# RPi_SPI_inputs_v01.net
KiCad netlist of a schematic drawn in EAGLE
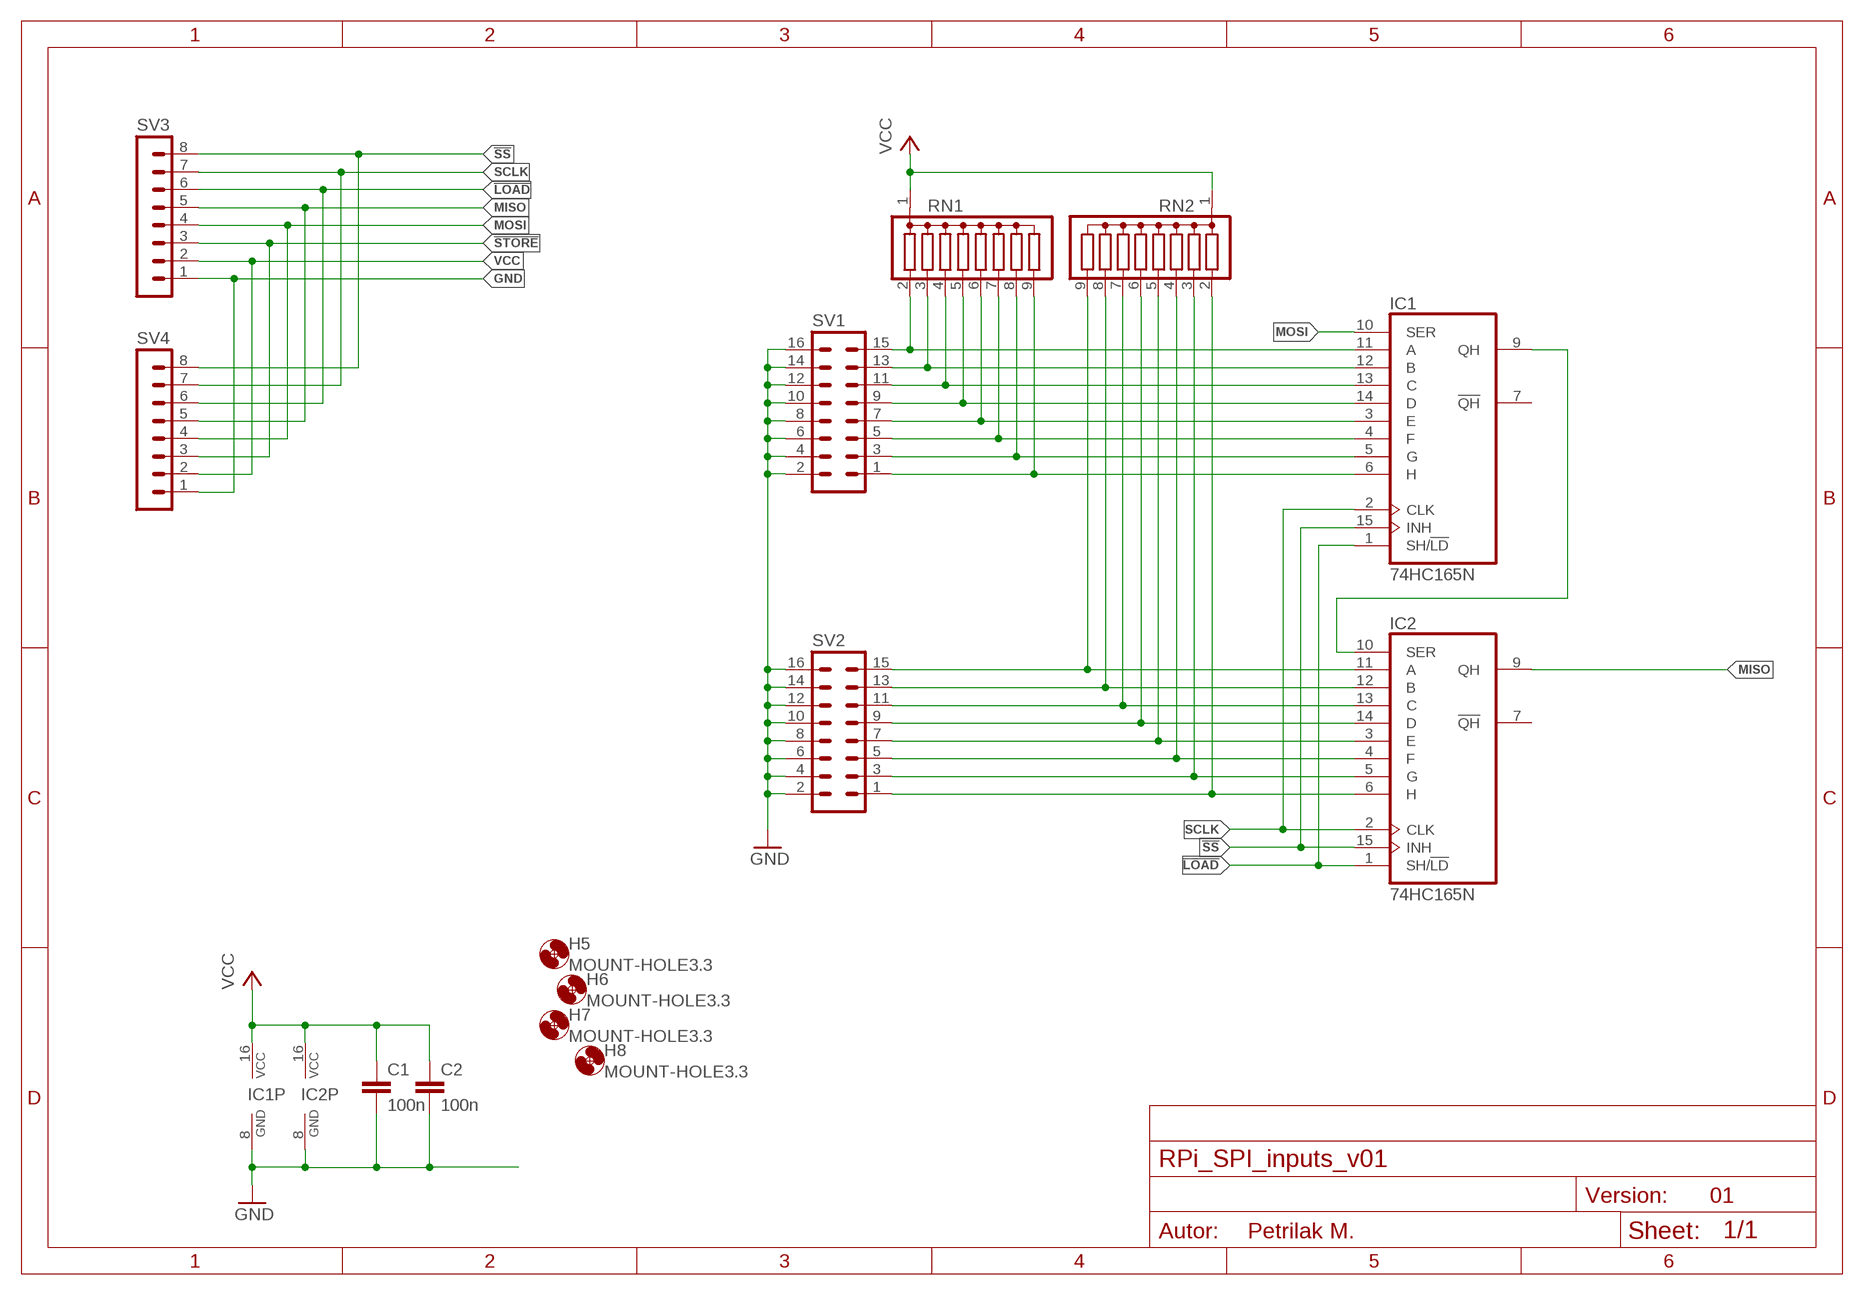
[diagram p0: schematic, sheet 1]

(export (version "E")
  (design (tool "Eeschema 10.0.6"))
  (components
    (comp (ref "C1")
      (value "100n")
      (footprint "eagle-import:C1206")
      (libsource (lib "eagle-import") (part "C-EUC1206"))
    )
    (comp (ref "C2")
      (value "100n")
      (footprint "eagle-import:C1206")
      (libsource (lib "eagle-import") (part "C-EUC1206"))
    )
    (comp (ref "H5")
      (value "MOUNT-HOLE3.3")
      (footprint "eagle-import:3,3")
      (libsource (lib "eagle-import") (part "MOUNT-HOLE3.3"))
    )
    (comp (ref "H6")
      (value "MOUNT-HOLE3.3")
      (footprint "eagle-import:3,3")
      (libsource (lib "eagle-import") (part "MOUNT-HOLE3.3"))
    )
    (comp (ref "H7")
      (value "MOUNT-HOLE3.3")
      (footprint "eagle-import:3,3")
      (libsource (lib "eagle-import") (part "MOUNT-HOLE3.3"))
    )
    (comp (ref "H8")
      (value "MOUNT-HOLE3.3")
      (footprint "eagle-import:3,3")
      (libsource (lib "eagle-import") (part "MOUNT-HOLE3.3"))
    )
    (comp (ref "IC1")
      (value "74HC165N")
      (footprint "eagle-import:DIL16")
      (libsource (lib "eagle-import") (part "74165NHC"))
    )
    (comp (ref "IC2")
      (value "74HC165N")
      (footprint "eagle-import:DIL16")
      (libsource (lib "eagle-import") (part "74165NHC"))
    )
    (comp (ref "RN1")
      (value "G08R")
      (footprint "eagle-import:SIL9")
      (libsource (lib "eagle-import") (part "G08R"))
    )
    (comp (ref "RN2")
      (value "G08R")
      (footprint "eagle-import:SIL9")
      (libsource (lib "eagle-import") (part "G08R"))
    )
    (comp (ref "SV1")
      (value "MA08-2-OP")
      (footprint "eagle-import:MA08-2-OP")
      (libsource (lib "eagle-import") (part "MA08-2-OP"))
    )
    (comp (ref "SV2")
      (value "MA08-2-OP")
      (footprint "eagle-import:MA08-2-OP")
      (libsource (lib "eagle-import") (part "MA08-2-OP"))
    )
    (comp (ref "SV3")
      (value "MA08-1")
      (footprint "eagle-import:MA08-1")
      (libsource (lib "eagle-import") (part "MA08-1"))
    )
    (comp (ref "SV4")
      (value "MA08-1")
      (footprint "eagle-import:MA08-1")
      (libsource (lib "eagle-import") (part "MA08-1"))
    )
  )
  (nets
    (net (code "1") (name "/~{LOAD}") (class "Default")
      (node (ref "IC1") (pin "1") (pinfunction "SH/~{LD}_1") (pintype "input"))
      (node (ref "IC2") (pin "1") (pinfunction "SH/~{LD}_1") (pintype "input"))
      (node (ref "SV3") (pin "6") (pinfunction "6_6") (pintype "passive"))
      (node (ref "SV4") (pin "6") (pinfunction "6_6") (pintype "passive"))
    )
    (net (code "2") (name "/~{SS}") (class "Default")
      (node (ref "IC1") (pin "15") (pinfunction "INH_15") (pintype "input"))
      (node (ref "IC2") (pin "15") (pinfunction "INH_15") (pintype "input"))
      (node (ref "SV3") (pin "8") (pinfunction "8_8") (pintype "passive"))
      (node (ref "SV4") (pin "8") (pinfunction "8_8") (pintype "passive"))
    )
    (net (code "3") (name "/~{STORE}") (class "Default")
      (node (ref "SV3") (pin "3") (pinfunction "3_3") (pintype "passive"))
      (node (ref "SV4") (pin "3") (pinfunction "3_3") (pintype "passive"))
    )
    (net (code "4") (name "GND") (class "Default")
      (node (ref "C1") (pin "2") (pinfunction "2_2") (pintype "passive"))
      (node (ref "C2") (pin "2") (pinfunction "2_2") (pintype "passive"))
      (node (ref "IC1") (pin "8") (pinfunction "GND_8") (pintype "power_in"))
      (node (ref "IC2") (pin "8") (pinfunction "GND_8") (pintype "power_in"))
      (node (ref "SV1") (pin "10") (pinfunction "10_10") (pintype "passive"))
      (node (ref "SV1") (pin "12") (pinfunction "12_12") (pintype "passive"))
      (node (ref "SV1") (pin "14") (pinfunction "14_14") (pintype "passive"))
      (node (ref "SV1") (pin "16") (pinfunction "16_16") (pintype "passive"))
      (node (ref "SV1") (pin "2") (pinfunction "2_2") (pintype "passive"))
      (node (ref "SV1") (pin "4") (pinfunction "4_4") (pintype "passive"))
      (node (ref "SV1") (pin "6") (pinfunction "6_6") (pintype "passive"))
      (node (ref "SV1") (pin "8") (pinfunction "8_8") (pintype "passive"))
      (node (ref "SV2") (pin "10") (pinfunction "10_10") (pintype "passive"))
      (node (ref "SV2") (pin "12") (pinfunction "12_12") (pintype "passive"))
      (node (ref "SV2") (pin "14") (pinfunction "14_14") (pintype "passive"))
      (node (ref "SV2") (pin "16") (pinfunction "16_16") (pintype "passive"))
      (node (ref "SV2") (pin "2") (pinfunction "2_2") (pintype "passive"))
      (node (ref "SV2") (pin "4") (pinfunction "4_4") (pintype "passive"))
      (node (ref "SV2") (pin "6") (pinfunction "6_6") (pintype "passive"))
      (node (ref "SV2") (pin "8") (pinfunction "8_8") (pintype "passive"))
      (node (ref "SV3") (pin "1") (pinfunction "1_1") (pintype "passive"))
      (node (ref "SV4") (pin "1") (pinfunction "1_1") (pintype "passive"))
    )
    (net (code "5") (name "MISO") (class "Default")
      (node (ref "IC2") (pin "9") (pinfunction "QH_9") (pintype "output"))
      (node (ref "SV3") (pin "5") (pinfunction "5_5") (pintype "passive"))
      (node (ref "SV4") (pin "5") (pinfunction "5_5") (pintype "passive"))
    )
    (net (code "6") (name "MOSI") (class "Default")
      (node (ref "IC1") (pin "10") (pinfunction "SER_10") (pintype "input"))
      (node (ref "SV3") (pin "4") (pinfunction "4_4") (pintype "passive"))
      (node (ref "SV4") (pin "4") (pinfunction "4_4") (pintype "passive"))
    )
    (net (code "7") (name "Net-(IC1A-A)") (class "Default")
      (node (ref "IC1") (pin "11") (pinfunction "A_11") (pintype "input"))
      (node (ref "RN1") (pin "2") (pinfunction "2_2") (pintype "passive"))
      (node (ref "SV1") (pin "15") (pinfunction "15_15") (pintype "passive"))
    )
    (net (code "8") (name "Net-(IC1A-B)") (class "Default")
      (node (ref "IC1") (pin "12") (pinfunction "B_12") (pintype "input"))
      (node (ref "RN1") (pin "3") (pinfunction "3_3") (pintype "passive"))
      (node (ref "SV1") (pin "13") (pinfunction "13_13") (pintype "passive"))
    )
    (net (code "9") (name "Net-(IC1A-C)") (class "Default")
      (node (ref "IC1") (pin "13") (pinfunction "C_13") (pintype "input"))
      (node (ref "RN1") (pin "4") (pinfunction "4_4") (pintype "passive"))
      (node (ref "SV1") (pin "11") (pinfunction "11_11") (pintype "passive"))
    )
    (net (code "10") (name "Net-(IC1A-D)") (class "Default")
      (node (ref "IC1") (pin "14") (pinfunction "D_14") (pintype "input"))
      (node (ref "RN1") (pin "5") (pinfunction "5_5") (pintype "passive"))
      (node (ref "SV1") (pin "9") (pinfunction "9_9") (pintype "passive"))
    )
    (net (code "11") (name "Net-(IC1A-E)") (class "Default")
      (node (ref "IC1") (pin "3") (pinfunction "E_3") (pintype "input"))
      (node (ref "RN1") (pin "6") (pinfunction "6_6") (pintype "passive"))
      (node (ref "SV1") (pin "7") (pinfunction "7_7") (pintype "passive"))
    )
    (net (code "12") (name "Net-(IC1A-F)") (class "Default")
      (node (ref "IC1") (pin "4") (pinfunction "F_4") (pintype "input"))
      (node (ref "RN1") (pin "7") (pinfunction "7_7") (pintype "passive"))
      (node (ref "SV1") (pin "5") (pinfunction "5_5") (pintype "passive"))
    )
    (net (code "13") (name "Net-(IC1A-G)") (class "Default")
      (node (ref "IC1") (pin "5") (pinfunction "G_5") (pintype "input"))
      (node (ref "RN1") (pin "8") (pinfunction "8_8") (pintype "passive"))
      (node (ref "SV1") (pin "3") (pinfunction "3_3") (pintype "passive"))
    )
    (net (code "14") (name "Net-(IC1A-H)") (class "Default")
      (node (ref "IC1") (pin "6") (pinfunction "H_6") (pintype "input"))
      (node (ref "RN1") (pin "9") (pinfunction "9_9") (pintype "passive"))
      (node (ref "SV1") (pin "1") (pinfunction "1_1") (pintype "passive"))
    )
    (net (code "15") (name "Net-(IC1A-QH)") (class "Default")
      (node (ref "IC1") (pin "9") (pinfunction "QH_9") (pintype "output"))
      (node (ref "IC2") (pin "10") (pinfunction "SER_10") (pintype "input"))
    )
    (net (code "16") (name "Net-(IC2A-A)") (class "Default")
      (node (ref "IC2") (pin "11") (pinfunction "A_11") (pintype "input"))
      (node (ref "RN2") (pin "9") (pinfunction "9_9") (pintype "passive"))
      (node (ref "SV2") (pin "15") (pinfunction "15_15") (pintype "passive"))
    )
    (net (code "17") (name "Net-(IC2A-B)") (class "Default")
      (node (ref "IC2") (pin "12") (pinfunction "B_12") (pintype "input"))
      (node (ref "RN2") (pin "8") (pinfunction "8_8") (pintype "passive"))
      (node (ref "SV2") (pin "13") (pinfunction "13_13") (pintype "passive"))
    )
    (net (code "18") (name "Net-(IC2A-C)") (class "Default")
      (node (ref "IC2") (pin "13") (pinfunction "C_13") (pintype "input"))
      (node (ref "RN2") (pin "7") (pinfunction "7_7") (pintype "passive"))
      (node (ref "SV2") (pin "11") (pinfunction "11_11") (pintype "passive"))
    )
    (net (code "19") (name "Net-(IC2A-D)") (class "Default")
      (node (ref "IC2") (pin "14") (pinfunction "D_14") (pintype "input"))
      (node (ref "RN2") (pin "6") (pinfunction "6_6") (pintype "passive"))
      (node (ref "SV2") (pin "9") (pinfunction "9_9") (pintype "passive"))
    )
    (net (code "20") (name "Net-(IC2A-E)") (class "Default")
      (node (ref "IC2") (pin "3") (pinfunction "E_3") (pintype "input"))
      (node (ref "RN2") (pin "5") (pinfunction "5_5") (pintype "passive"))
      (node (ref "SV2") (pin "7") (pinfunction "7_7") (pintype "passive"))
    )
    (net (code "21") (name "Net-(IC2A-F)") (class "Default")
      (node (ref "IC2") (pin "4") (pinfunction "F_4") (pintype "input"))
      (node (ref "RN2") (pin "4") (pinfunction "4_4") (pintype "passive"))
      (node (ref "SV2") (pin "5") (pinfunction "5_5") (pintype "passive"))
    )
    (net (code "22") (name "Net-(IC2A-G)") (class "Default")
      (node (ref "IC2") (pin "5") (pinfunction "G_5") (pintype "input"))
      (node (ref "RN2") (pin "3") (pinfunction "3_3") (pintype "passive"))
      (node (ref "SV2") (pin "3") (pinfunction "3_3") (pintype "passive"))
    )
    (net (code "23") (name "Net-(IC2A-H)") (class "Default")
      (node (ref "IC2") (pin "6") (pinfunction "H_6") (pintype "input"))
      (node (ref "RN2") (pin "2") (pinfunction "2_2") (pintype "passive"))
      (node (ref "SV2") (pin "1") (pinfunction "1_1") (pintype "passive"))
    )
    (net (code "24") (name "SCLK") (class "Default")
      (node (ref "IC1") (pin "2") (pinfunction "CLK_2") (pintype "input"))
      (node (ref "IC2") (pin "2") (pinfunction "CLK_2") (pintype "input"))
      (node (ref "SV3") (pin "7") (pinfunction "7_7") (pintype "passive"))
      (node (ref "SV4") (pin "7") (pinfunction "7_7") (pintype "passive"))
    )
    (net (code "25") (name "VCC") (class "Default")
      (node (ref "C1") (pin "1") (pinfunction "1_1") (pintype "passive"))
      (node (ref "C2") (pin "1") (pinfunction "1_1") (pintype "passive"))
      (node (ref "IC1") (pin "16") (pinfunction "VCC_16") (pintype "power_in"))
      (node (ref "IC2") (pin "16") (pinfunction "VCC_16") (pintype "power_in"))
      (node (ref "RN1") (pin "1") (pinfunction "1_1") (pintype "passive"))
      (node (ref "RN2") (pin "1") (pinfunction "1_1") (pintype "passive"))
      (node (ref "SV3") (pin "2") (pinfunction "2_2") (pintype "passive"))
      (node (ref "SV4") (pin "2") (pinfunction "2_2") (pintype "passive"))
    )
    (net (code "26") (name "unconnected-(IC1A-~{QH}-Pad7)") (class "Default")
      (node (ref "IC1") (pin "7") (pinfunction "~{QH}_7") (pintype "output"))
    )
    (net (code "27") (name "unconnected-(IC2A-~{QH}-Pad7)") (class "Default")
      (node (ref "IC2") (pin "7") (pinfunction "~{QH}_7") (pintype "output"))
    )
  )
)
